# NLOS_PCB.net
KiCad netlist of a schematic drawn in Altium Designer
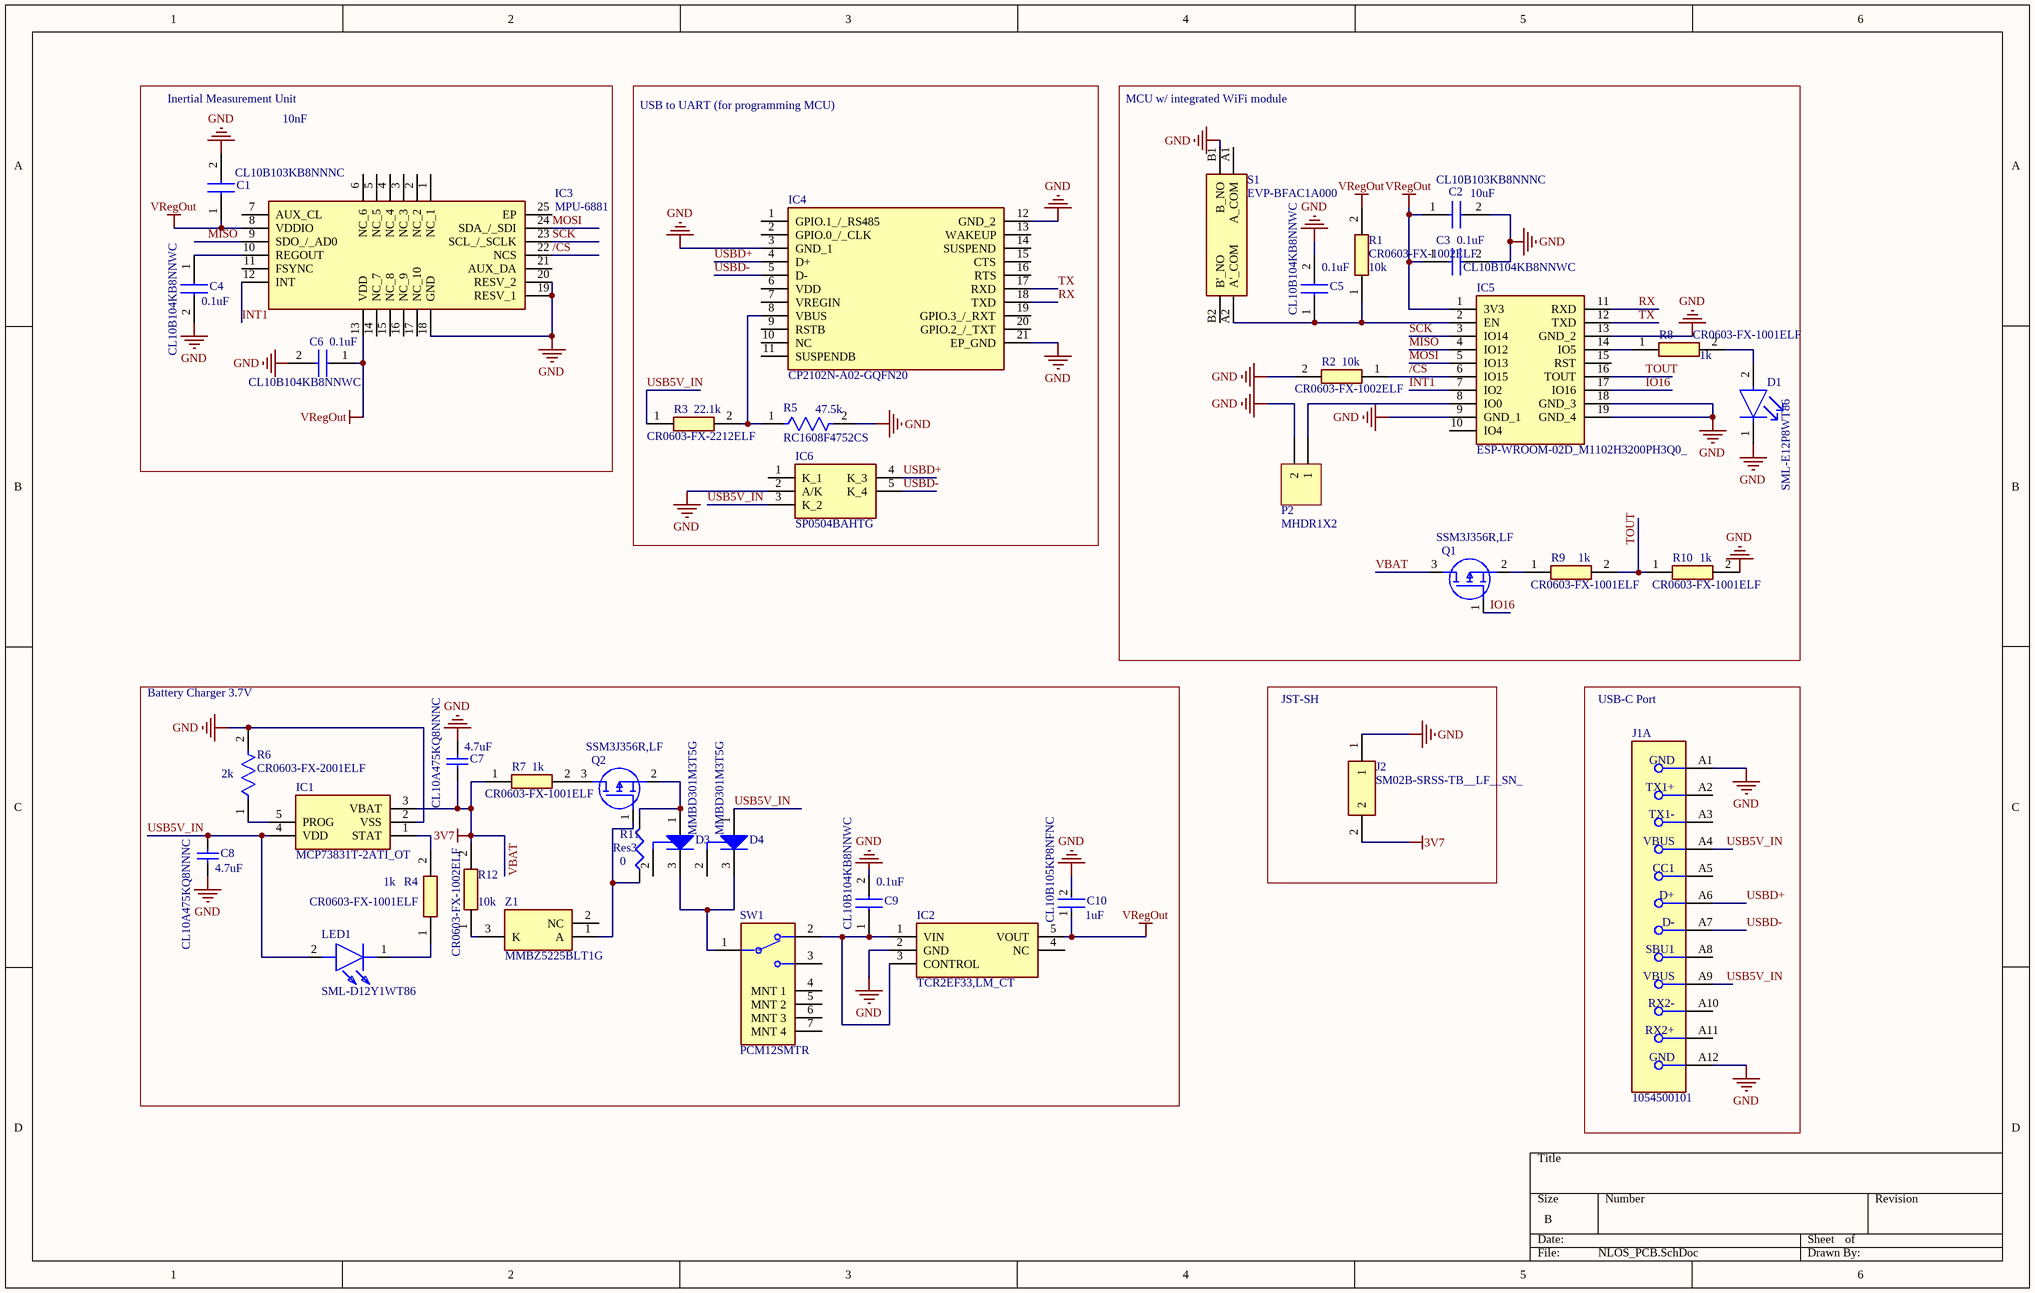
[diagram p0: NLOS_PCB.SchDoc]

(export (version "E")
  (design (tool "Eeschema 10.0.6"))
  (components
    (comp (ref "C1")
      (value "CL10B103KB8NNNC")
      (footprint "CAPC1608X90N")
      (description "Capacitor")
      (fields (field (name "MOUSER PART NUMBER") "187-CL10B103KB8NNNC"))
      (libsource (lib "*") (part "CL10B103KB8NNNC"))
    )
    (comp (ref "C2")
      (value "CL10B103KB8NNNC")
      (footprint "CAPC1608X90N")
      (description "Capacitor")
      (fields (field (name "MOUSER PART NUMBER") "187-CL10B103KB8NNNC"))
      (libsource (lib "*") (part "CL10B103KB8NNNC"))
    )
    (comp (ref "C3")
      (value "CL10B104KB8NNWC")
      (footprint "CAPC1608X90N")
      (description "Capacitor")
      (libsource (lib "*") (part "CL10B104KB8NNWC"))
    )
    (comp (ref "C4")
      (value "CL10B104KB8NNWC")
      (footprint "CAPC1608X90N")
      (description "Capacitor")
      (libsource (lib "*") (part "CL10B104KB8NNWC"))
    )
    (comp (ref "C5")
      (value "CL10B104KB8NNWC")
      (footprint "CAPC1608X90N")
      (description "Capacitor")
      (libsource (lib "*") (part "CL10B104KB8NNWC"))
    )
    (comp (ref "C6")
      (value "CL10B104KB8NNWC")
      (footprint "CAPC1608X90N")
      (description "Capacitor")
      (libsource (lib "*") (part "CL10B104KB8NNWC"))
    )
    (comp (ref "C7")
      (value "CL10A475KQ8NNNC")
      (footprint "CAPC1608X90X30LL10T20")
      (description "Chip Capacitor, 4.7 uF, +/- 10%, 6.3 V, -55 to 85 degC, 0603 (1608 Metric), RoHS, Tape and Reel")
      (fields (field (name "MANUFACTURER") "Samsung Electro-Mechanics"))
      (libsource (lib "Altium Content Vault") (part "CAP-NP-2"))
    )
    (comp (ref "C8")
      (value "CL10A475KQ8NNNC")
      (footprint "CAPC1608X90X30LL10T20")
      (description "Chip Capacitor, 4.7 uF, +/- 10%, 6.3 V, -55 to 85 degC, 0603 (1608 Metric), RoHS, Tape and Reel")
      (fields (field (name "MANUFACTURER") "Samsung Electro-Mechanics"))
      (libsource (lib "Altium Content Vault") (part "CAP-NP-2"))
    )
    (comp (ref "C9")
      (value "CL10B104KB8NNWC")
      (footprint "CAPC1608X90N")
      (description "Capacitor")
      (libsource (lib "*") (part "CL10B104KB8NNWC"))
    )
    (comp (ref "C10")
      (value "CL10B105KP8NFNC")
      (footprint "FP-CL10-IPC_B")
      (description "Cap Ceramic 1uF 10V X7R ±10% Pad SMD 0603 +125°C T/R")
      (fields (field (name "TOLERANCE") "10%"))
      (libsource (lib "Altium Content Vault") (part "b4654b650e69147ec39a6b967a45e02"))
    )
    (comp (ref "D1")
      (value "SML-E12P8WT86")
      (footprint "FP-SML-E12-MFG")
      (description "LED GREEN DIFFUSED 0603 SMD")
      (fields
        (field (name "MANUFACTURER") "Rohm")
        (field (name "OCTOPART") "https://octopart.com/sml-e12p8wt86-rohm-9290854")
      )
      (libsource (lib "Altium Content Vault") (part "8706943c75ba83719d021d2fdc84c58"))
    )
    (comp (ref "D3")
      (value "MMBD301M3T5G")
      (footprint "ONSC-SOT-723-3-631AA-01_V")
      (description "Silicon Hot-Carrier Diode, Schottky Barrier Diode, 3-Pin SOT-723, Pb-Free, Tape and Reel")
      (fields (field (name "MANUFACTURER") "On Semiconductor"))
      (libsource (lib "Altium Content Vault") (part "ONSC-D-A1K3-3"))
    )
    (comp (ref "D4")
      (value "MMBD301M3T5G")
      (footprint "ONSC-SOT-723-3-631AA-01_V")
      (description "Silicon Hot-Carrier Diode, Schottky Barrier Diode, 3-Pin SOT-723, Pb-Free, Tape and Reel")
      (fields (field (name "MANUFACTURER") "On Semiconductor"))
      (libsource (lib "Altium Content Vault") (part "ONSC-D-A1K3-3"))
    )
    (comp (ref "IC1")
      (value "MCP73831T-2ATI_OT")
      (footprint "SamacSys:SOT95P270X145-5N")
      (description "Integrated Circuit")
      (fields
        (field (name "MANUFACTURER_PART_NUMBER") "MCP73831T-2ATI/OT")
        (field (name "MOUSER PART NUMBER") "579-MCP73831T-2ATIOT")
      )
      (libsource (lib "*") (part "MCP73831T-2ATI_OT"))
    )
    (comp (ref "IC2")
      (value "TCR2EF33,LM_CT")
      (footprint "SamacSys:SOT-25")
      (description "Integrated Circuit")
      (fields
        (field (name "MANUFACTURER_PART_NUMBER") "TCR2EF33,LM(CT")
        (field (name "MOUSER PART NUMBER") "757-TCR2EF33LMCT")
      )
      (libsource (lib "*") (part "TCR2EF33,LM_CT"))
    )
    (comp (ref "IC3")
      (value "MPU-6881")
      (footprint "SamacSys:QFN40P300X300X95-25N-D")
      (description "Integrated Circuit")
      (fields (field (name "MOUSER PART NUMBER") "410-MPU-6881"))
      (libsource (lib "*") (part "MPU-6881"))
    )
    (comp (ref "IC4")
      (value "CP2102N-A02-GQFN20")
      (footprint "SamacSys:CP2102NA02GQFN20")
      (description "Integrated Circuit")
      (fields (field (name "MOUSER PART NUMBER") "634-CP2102NA02GQFN20"))
      (libsource (lib "*") (part "CP2102N-A02-GQFN20"))
    )
    (comp (ref "IC5")
      (value "ESP-WROOM-02D_M1102H3200PH3Q0_")
      (footprint "SamacSys:ESPWROOM02DM1102H3200PH3Q0")
      (description "Integrated Circuit")
      (fields
        (field (name "MANUFACTURER_PART_NUMBER") "ESP-WROOM-02D(M1102H3200PH3Q0)")
        (field (name "MOUSER PART NUMBER") "356-ESPWROOM02D(4MB)")
      )
      (libsource (lib "*") (part "ESP-WROOM-02D_M1102H3200PH3Q0_"))
    )
    (comp (ref "IC6")
      (value "SP0504BAHTG")
      (footprint "SamacSys:SOT95P280X145-5N")
      (description "Integrated Circuit")
      (fields (field (name "MOUSER PART NUMBER") "576-SP0504BAHTG"))
      (libsource (lib "*") (part "SP0504BAHTG"))
    )
    (comp (ref "J1")
      (value "1054500101")
      (footprint "FP-1054500101-MFG")
      (description "CONN RCP USB3.1 TYPEC 24P SMD RA")
      (fields
        (field (name "MANUFACTURER") "Molex")
        (field (name "OCTOPART") "https://octopart.com/105450-0101-molex-68082325")
      )
      (libsource (lib "Altium Content Vault") (part "9808b19ecaf079fb99eed69f0495cd0"))
    )
    (comp (ref "J2")
      (value "SM02B-SRSS-TB__LF__SN_")
      (footprint "SamacSys:SM02B-SRSS-TB")
      (description "Connector")
      (fields (field (name "MANUFACTURER_PART_NUMBER") "SM02B-SRSS-TB (LF)(SN)"))
      (libsource (lib "*") (part "SM02B-SRSS-TB__LF__SN_"))
    )
    (comp (ref "LED1")
      (value "SML-D12Y1WT86")
      (footprint "SamacSys:LEDC1608X55N")
      (description "LED")
      (fields (field (name "MOUSER PART NUMBER") "755-SML-D12Y1WT86"))
      (libsource (lib "*") (part "SML-D12Y1WT86"))
    )
    (comp (ref "P2")
      (value "MHDR1X2")
      (footprint "MHDR1X2")
      (description "Header, 2-Pin")
      (fields (field (name "PUBLISHER") "Altium Limited"))
      (libsource (lib "Miscellaneous Connectors") (part "MHDR1X2"))
    )
    (comp (ref "Q1")
      (value "SSM3J356R,LF")
      (footprint "SOT96P240X110-3N")
      (description "MOSFET (P-Channel)")
      (fields (field (name "MOUSER PART NUMBER") "757-SSM3J356RLF"))
      (libsource (lib "*") (part "SSM3J356R,LF"))
    )
    (comp (ref "Q2")
      (value "SSM3J356R,LF")
      (footprint "SOT96P240X110-3N")
      (description "MOSFET (P-Channel)")
      (fields (field (name "MOUSER PART NUMBER") "757-SSM3J356RLF"))
      (libsource (lib "*") (part "SSM3J356R,LF"))
    )
    (comp (ref "R1")
      (value "CR0603-FX-1002ELF")
      (footprint "SamacSys:RESC1608X55N")
      (description "Resistor")
      (fields (field (name "MOUSER PART NUMBER") "652-CR0603FX-1002ELF"))
      (libsource (lib "*") (part "CR0603-FX-1002ELF"))
    )
    (comp (ref "R2")
      (value "CR0603-FX-1002ELF")
      (footprint "RESC1608X55N")
      (description "Resistor")
      (fields (field (name "MOUSER PART NUMBER") "652-CR0603FX-1002ELF"))
      (libsource (lib "") (part "CR0603-FX-1002ELF_1"))
    )
    (comp (ref "R3")
      (value "CR0603-FX-2212ELF")
      (footprint "RESC1608X55N")
      (description "Resistor")
      (fields (field (name "MOUSER PART NUMBER") "652-CR0603FX-2212ELF"))
      (libsource (lib "*") (part "CR0603-FX-2212ELF"))
    )
    (comp (ref "R4")
      (value "CR0603-FX-1001ELF")
      (footprint "RESC1608X55N")
      (description "Resistor")
      (fields (field (name "MOUSER PART NUMBER") "652-CR0603FX-1001ELF"))
      (libsource (lib "") (part "CR0603-FX-1001ELF_1"))
    )
    (comp (ref "R5")
      (value "RC1608F4752CS")
      (footprint "FP-RC1608-MFG")
      (description "Res Thick Film 0603 47.5kΩ 1% 0.1W ±100ppm/°C Molded SMD T/R")
      (fields (field (name "TOLERANCE") "1%"))
      (libsource (lib "Altium Content Vault") (part "1029c3af85768c4190bb7ad29bc67b5"))
    )
    (comp (ref "R6")
      (value "CR0603-FX-2001ELF")
      (footprint "FP-CR0603-IPC_A")
      (description "Thick Film Chip Resistors 0603 2kΩ 0.1W 1% 100ppm/°C")
      (fields (field (name "TOLERANCE") "1%"))
      (libsource (lib "Altium Content Vault") (part "1029c3af85768c4190bb7ad29bc67b5"))
    )
    (comp (ref "R7")
      (value "CR0603-FX-1001ELF")
      (footprint "RESC1608X55N")
      (description "Resistor")
      (fields (field (name "MOUSER PART NUMBER") "652-CR0603FX-1001ELF"))
      (libsource (lib "*") (part "CR0603-FX-1001ELF"))
    )
    (comp (ref "R8")
      (value "CR0603-FX-1001ELF")
      (footprint "RESC1608X55N")
      (description "Resistor")
      (fields (field (name "MOUSER PART NUMBER") "652-CR0603FX-1001ELF"))
      (libsource (lib "*") (part "CR0603-FX-1001ELF"))
    )
    (comp (ref "R9")
      (value "CR0603-FX-1001ELF")
      (footprint "RESC1608X55N")
      (description "Resistor")
      (fields (field (name "MOUSER PART NUMBER") "652-CR0603FX-1001ELF"))
      (libsource (lib "*") (part "CR0603-FX-1001ELF"))
    )
    (comp (ref "R10")
      (value "CR0603-FX-1001ELF")
      (footprint "RESC1608X55N")
      (description "Resistor")
      (fields (field (name "MOUSER PART NUMBER") "652-CR0603FX-1001ELF"))
      (libsource (lib "*") (part "CR0603-FX-1001ELF"))
    )
    (comp (ref "R11")
      (value "Res3")
      (footprint "J1-0603")
      (description "Resistor")
      (fields (field (name "ALTIUM_VALUE") "0") (field (name "PUBLISHER") "Altium Limited"))
      (libsource (lib "Miscellaneous Devices") (part "Res3"))
    )
    (comp (ref "R12")
      (value "CR0603-FX-1002ELF")
      (footprint "RESC1608X55N")
      (description "Resistor")
      (fields (field (name "MOUSER PART NUMBER") "652-CR0603FX-1002ELF"))
      (libsource (lib "SamacSys") (part "CR0603-FX-1002ELF"))
    )
    (comp (ref "S1")
      (value "EVP-BFAC1A000")
      (footprint "SamacSys:EVPBFAC1A000")
      (description "Switch")
      (fields (field (name "MOUSER PART NUMBER") "667-EVP-BFAC1A000"))
      (libsource (lib "*") (part "EVP-BFAC1A000"))
    )
    (comp (ref "SW1")
      (value "PCM12SMTR")
      (footprint "FP-PCM12SMTR-MFG")
      (description "SWITCH SLIDE SPDT 300MA 6V")
      (libsource (lib "Altium Content Vault") (part "1a3f67d7e2b5469b171eeab59ffb4d2"))
    )
    (comp (ref "Z1")
      (value "MMBZ5225BLT1G")
      (footprint "SamacSys:SOT96P237X111-3N")
      (description "Zener Diode")
      (fields (field (name "MOUSER PART NUMBER") "863-MMBZ5225BLT1G"))
      (libsource (lib "*") (part "MMBZ5225BLT1G"))
    )
  )
  (nets
    (net (code "1") (name "/INT1") (class "Default")
      (node (ref "IC3") (pin "12") (pinfunction "INT_12") (pintype "passive"))
      (node (ref "IC5") (pin "7") (pinfunction "IO2_7") (pintype "passive"))
    )
    (net (code "2") (name "/IO16") (class "Default")
      (node (ref "IC5") (pin "17") (pinfunction "IO16_17") (pintype "passive"))
      (node (ref "Q1") (pin "1") (pinfunction "G_1") (pintype "passive"))
    )
    (net (code "3") (name "/MISO") (class "Default")
      (node (ref "IC3") (pin "9") (pinfunction "SDO_/_AD0_9") (pintype "passive"))
      (node (ref "IC5") (pin "4") (pinfunction "IO12_4") (pintype "passive"))
    )
    (net (code "4") (name "/MOSI") (class "Default")
      (node (ref "IC3") (pin "24") (pinfunction "SDA_/_SDI_24") (pintype "passive"))
      (node (ref "IC5") (pin "5") (pinfunction "IO13_5") (pintype "passive"))
    )
    (net (code "5") (name "/RX") (class "Default")
      (node (ref "IC4") (pin "18") (pinfunction "TXD_18") (pintype "passive"))
      (node (ref "IC5") (pin "11") (pinfunction "RXD_11") (pintype "passive"))
    )
    (net (code "6") (name "/SCK") (class "Default")
      (node (ref "IC3") (pin "23") (pinfunction "SCL_/_SCLK_23") (pintype "passive"))
      (node (ref "IC5") (pin "3") (pinfunction "IO14_3") (pintype "passive"))
    )
    (net (code "7") (name "/TOUT") (class "Default")
      (node (ref "IC5") (pin "16") (pinfunction "TOUT_16") (pintype "passive"))
      (node (ref "R10") (pin "1") (pinfunction "1_1") (pintype "passive"))
      (node (ref "R9") (pin "2") (pinfunction "2_2") (pintype "passive"))
    )
    (net (code "8") (name "/TX") (class "Default")
      (node (ref "IC4") (pin "17") (pinfunction "RXD_17") (pintype "passive"))
      (node (ref "IC5") (pin "12") (pinfunction "TXD_12") (pintype "passive"))
    )
    (net (code "9") (name "/USB5V_IN") (class "Default")
      (node (ref "C8") (pin "2") (pinfunction "2_2") (pintype "passive"))
      (node (ref "D4") (pin "1") (pinfunction "A_1") (pintype "passive"))
      (node (ref "IC1") (pin "4") (pinfunction "VDD_4") (pintype "power_in"))
      (node (ref "IC6") (pin "3") (pinfunction "K_2_3") (pintype "passive"))
      (node (ref "J1") (pin "A4") (pinfunction "VBUS_A4") (pintype "passive"))
      (node (ref "J1") (pin "A9") (pinfunction "VBUS_A9") (pintype "passive"))
      (node (ref "LED1") (pin "2") (pinfunction "A_2") (pintype "passive"))
      (node (ref "R3") (pin "1") (pinfunction "1_1") (pintype "passive"))
    )
    (net (code "10") (name "/USBD+") (class "Default")
      (node (ref "IC4") (pin "4") (pinfunction "D+_4") (pintype "passive"))
      (node (ref "IC6") (pin "4") (pinfunction "K_3_4") (pintype "passive"))
      (node (ref "J1") (pin "A6") (pinfunction "D+_A6") (pintype "passive"))
    )
    (net (code "11") (name "/USBD-") (class "Default")
      (node (ref "IC4") (pin "5") (pinfunction "D-_5") (pintype "passive"))
      (node (ref "IC6") (pin "5") (pinfunction "K_4_5") (pintype "passive"))
      (node (ref "J1") (pin "A7") (pinfunction "D-_A7") (pintype "passive"))
    )
    (net (code "12") (name "/{slash}CS") (class "Default")
      (node (ref "IC3") (pin "22") (pinfunction "NCS_22") (pintype "passive"))
      (node (ref "IC5") (pin "6") (pinfunction "IO15_6") (pintype "passive"))
      (node (ref "R2") (pin "1") (pinfunction "1_1") (pintype "passive"))
    )
    (net (code "13") (name "3V7") (class "Default")
      (node (ref "C7") (pin "1") (pinfunction "1_1") (pintype "passive"))
      (node (ref "IC1") (pin "3") (pinfunction "VBAT_3") (pintype "passive"))
      (node (ref "J2") (pin "2") (pinfunction "2_2") (pintype "passive"))
      (node (ref "Q1") (pin "3") (pinfunction "D_3") (pintype "passive"))
      (node (ref "R12") (pin "2") (pinfunction "2_2") (pintype "passive"))
      (node (ref "R7") (pin "1") (pinfunction "1_1") (pintype "passive"))
    )
    (net (code "14") (name "GND") (class "Default")
      (node (ref "C1") (pin "2") (pinfunction "2_2") (pintype "passive"))
      (node (ref "C10") (pin "2") (pinfunction "2_2") (pintype "passive"))
      (node (ref "C2") (pin "2") (pinfunction "2_2") (pintype "passive"))
      (node (ref "C3") (pin "2") (pinfunction "2_2") (pintype "passive"))
      (node (ref "C4") (pin "2") (pinfunction "2_2") (pintype "passive"))
      (node (ref "C5") (pin "2") (pinfunction "2_2") (pintype "passive"))
      (node (ref "C6") (pin "2") (pinfunction "2_2") (pintype "passive"))
      (node (ref "C7") (pin "2") (pinfunction "2_2") (pintype "passive"))
      (node (ref "C8") (pin "1") (pinfunction "1_1") (pintype "passive"))
      (node (ref "C9") (pin "2") (pinfunction "2_2") (pintype "passive"))
      (node (ref "D1") (pin "1") (pinfunction "C_1") (pintype "passive"))
      (node (ref "IC1") (pin "2") (pinfunction "VSS_2") (pintype "power_in"))
      (node (ref "IC2") (pin "2") (pinfunction "GND_2") (pintype "passive"))
      (node (ref "IC3") (pin "18") (pinfunction "GND_18") (pintype "passive"))
      (node (ref "IC3") (pin "19") (pinfunction "RESV_1_19") (pintype "passive"))
      (node (ref "IC3") (pin "20") (pinfunction "RESV_2_20") (pintype "passive"))
      (node (ref "IC4") (pin "12") (pinfunction "GND_2_12") (pintype "passive"))
      (node (ref "IC4") (pin "21") (pinfunction "EP_GND_21") (pintype "passive"))
      (node (ref "IC4") (pin "3") (pinfunction "GND_1_3") (pintype "passive"))
      (node (ref "IC5") (pin "13") (pinfunction "GND_2_13") (pintype "passive"))
      (node (ref "IC5") (pin "18") (pinfunction "GND_3_18") (pintype "passive"))
      (node (ref "IC5") (pin "19") (pinfunction "GND_4_19") (pintype "passive"))
      (node (ref "IC5") (pin "9") (pinfunction "GND_1_9") (pintype "passive"))
      (node (ref "IC6") (pin "2") (pinfunction "A/K_2") (pintype "passive"))
      (node (ref "J1") (pin "A1") (pinfunction "GND_A1") (pintype "passive"))
      (node (ref "J1") (pin "A12") (pinfunction "GND_A12") (pintype "passive"))
      (node (ref "J2") (pin "1") (pinfunction "1_1") (pintype "passive"))
      (node (ref "P2") (pin "2") (pinfunction "2_2") (pintype "passive"))
      (node (ref "R10") (pin "2") (pinfunction "2_2") (pintype "passive"))
      (node (ref "R2") (pin "2") (pinfunction "2_2") (pintype "passive"))
      (node (ref "R5") (pin "2") (pinfunction "2_2") (pintype "passive"))
      (node (ref "R6") (pin "2") (pinfunction "2_2") (pintype "passive"))
      (node (ref "S1") (pin "B1") (pinfunction "B_NO_B1") (pintype "passive"))
    )
    (net (code "15") (name "Net-(D1-A)") (class "Default")
      (node (ref "D1") (pin "2") (pinfunction "A_2") (pintype "passive"))
      (node (ref "R8") (pin "2") (pinfunction "2_2") (pintype "passive"))
    )
    (net (code "16") (name "Net-(D3-A)") (class "Default")
      (node (ref "D3") (pin "1") (pinfunction "A_1") (pintype "passive"))
      (node (ref "Q2") (pin "2") (pinfunction "S_2") (pintype "passive"))
      (node (ref "R11") (pin "2") (pinfunction "2_2") (pintype "passive"))
    )
    (net (code "17") (name "Net-(D3-K)") (class "Default")
      (node (ref "D3") (pin "3") (pinfunction "K_3") (pintype "passive"))
      (node (ref "D4") (pin "3") (pinfunction "K_3") (pintype "passive"))
      (node (ref "SW1") (pin "1") (pinfunction "1_1") (pintype "passive"))
    )
    (net (code "18") (name "Net-(IC1-PROG)") (class "Default")
      (node (ref "IC1") (pin "5") (pinfunction "PROG_5") (pintype "passive"))
      (node (ref "R6") (pin "1") (pinfunction "1_1") (pintype "passive"))
    )
    (net (code "19") (name "Net-(IC1-STAT)") (class "Default")
      (node (ref "IC1") (pin "1") (pinfunction "STAT_1") (pintype "passive"))
      (node (ref "R4") (pin "2") (pinfunction "2_2") (pintype "passive"))
    )
    (net (code "20") (name "Net-(IC2-CONTROL)") (class "Default")
      (node (ref "C9") (pin "1") (pinfunction "1_1") (pintype "passive"))
      (node (ref "IC2") (pin "1") (pinfunction "VIN_1") (pintype "passive"))
      (node (ref "IC2") (pin "3") (pinfunction "CONTROL_3") (pintype "passive"))
      (node (ref "SW1") (pin "2") (pinfunction "2_2") (pintype "passive"))
    )
    (net (code "21") (name "Net-(IC3-REGOUT)") (class "Default")
      (node (ref "C4") (pin "1") (pinfunction "1_1") (pintype "passive"))
      (node (ref "IC3") (pin "10") (pinfunction "REGOUT_10") (pintype "passive"))
    )
    (net (code "22") (name "Net-(IC4-VBUS)") (class "Default")
      (node (ref "IC4") (pin "8") (pinfunction "VBUS_8") (pintype "passive"))
      (node (ref "R3") (pin "2") (pinfunction "2_2") (pintype "passive"))
      (node (ref "R5") (pin "1") (pinfunction "1_1") (pintype "passive"))
    )
    (net (code "23") (name "Net-(IC5-EN)") (class "Default")
      (node (ref "C5") (pin "1") (pinfunction "1_1") (pintype "passive"))
      (node (ref "IC5") (pin "2") (pinfunction "EN_2") (pintype "passive"))
      (node (ref "R1") (pin "1") (pinfunction "1_1") (pintype "passive"))
      (node (ref "S1") (pin "A2") (pinfunction "A'_COM_A2") (pintype "passive"))
    )
    (net (code "24") (name "Net-(IC5-IO0)") (class "Default")
      (node (ref "IC5") (pin "8") (pinfunction "IO0_8") (pintype "passive"))
      (node (ref "P2") (pin "1") (pinfunction "1_1") (pintype "passive"))
    )
    (net (code "25") (name "Net-(IC5-IO5)") (class "Default")
      (node (ref "IC5") (pin "14") (pinfunction "IO5_14") (pintype "passive"))
      (node (ref "R8") (pin "1") (pinfunction "1_1") (pintype "passive"))
    )
    (net (code "26") (name "Net-(LED1-K)") (class "Default")
      (node (ref "LED1") (pin "1") (pinfunction "K_1") (pintype "passive"))
      (node (ref "R4") (pin "1") (pinfunction "1_1") (pintype "passive"))
    )
    (net (code "27") (name "Net-(Q1-S)") (class "Default")
      (node (ref "Q1") (pin "2") (pinfunction "S_2") (pintype "passive"))
      (node (ref "R9") (pin "1") (pinfunction "1_1") (pintype "passive"))
    )
    (net (code "28") (name "Net-(Q2-D)") (class "Default")
      (node (ref "Q2") (pin "3") (pinfunction "D_3") (pintype "passive"))
      (node (ref "R7") (pin "2") (pinfunction "2_2") (pintype "passive"))
    )
    (net (code "29") (name "Net-(Q2-G)") (class "Default")
      (node (ref "Q2") (pin "1") (pinfunction "G_1") (pintype "passive"))
      (node (ref "R11") (pin "1") (pinfunction "1_1") (pintype "passive"))
      (node (ref "Z1") (pin "1") (pinfunction "A_1") (pintype "passive"))
    )
    (net (code "30") (name "Net-(Z1-K)") (class "Default")
      (node (ref "R12") (pin "1") (pinfunction "1_1") (pintype "passive"))
      (node (ref "Z1") (pin "3") (pinfunction "K_3") (pintype "passive"))
    )
    (net (code "31") (name "VRegOut") (class "Default")
      (node (ref "C1") (pin "1") (pinfunction "1_1") (pintype "passive"))
      (node (ref "C10") (pin "1") (pinfunction "1_1") (pintype "passive"))
      (node (ref "C2") (pin "1") (pinfunction "1_1") (pintype "passive"))
      (node (ref "C3") (pin "1") (pinfunction "1_1") (pintype "passive"))
      (node (ref "C6") (pin "1") (pinfunction "1_1") (pintype "passive"))
      (node (ref "IC2") (pin "5") (pinfunction "VOUT_5") (pintype "passive"))
      (node (ref "IC3") (pin "13") (pinfunction "VDD_13") (pintype "passive"))
      (node (ref "IC3") (pin "8") (pinfunction "VDDIO_8") (pintype "passive"))
      (node (ref "IC5") (pin "1") (pinfunction "3V3_1") (pintype "passive"))
      (node (ref "R1") (pin "2") (pinfunction "2_2") (pintype "passive"))
    )
    (net (code "32") (name "unconnected-(D3-NC-Pad2)") (class "Default")
      (node (ref "D3") (pin "2") (pinfunction "NC_2") (pintype "passive"))
    )
    (net (code "33") (name "unconnected-(D4-NC-Pad2)") (class "Default")
      (node (ref "D4") (pin "2") (pinfunction "NC_2") (pintype "passive"))
    )
    (net (code "34") (name "unconnected-(IC2-NC-Pad4)") (class "Default")
      (node (ref "IC2") (pin "4") (pinfunction "NC_4") (pintype "passive"))
    )
    (net (code "35") (name "unconnected-(IC3-AUX_CL-Pad7)") (class "Default")
      (node (ref "IC3") (pin "7") (pinfunction "AUX_CL_7") (pintype "passive"))
    )
    (net (code "36") (name "unconnected-(IC3-AUX_DA-Pad21)") (class "Default")
      (node (ref "IC3") (pin "21") (pinfunction "AUX_DA_21") (pintype "passive"))
    )
    (net (code "37") (name "unconnected-(IC3-EP-Pad25)") (class "Default")
      (node (ref "IC3") (pin "25") (pinfunction "EP_25") (pintype "passive"))
    )
    (net (code "38") (name "unconnected-(IC3-FSYNC-Pad11)") (class "Default")
      (node (ref "IC3") (pin "11") (pinfunction "FSYNC_11") (pintype "passive"))
    )
    (net (code "39") (name "unconnected-(IC3-NC_1-Pad1)") (class "Default")
      (node (ref "IC3") (pin "1") (pinfunction "NC_1_1") (pintype "passive"))
    )
    (net (code "40") (name "unconnected-(IC3-NC_2-Pad2)") (class "Default")
      (node (ref "IC3") (pin "2") (pinfunction "NC_2_2") (pintype "passive"))
    )
    (net (code "41") (name "unconnected-(IC3-NC_3-Pad3)") (class "Default")
      (node (ref "IC3") (pin "3") (pinfunction "NC_3_3") (pintype "passive"))
    )
    (net (code "42") (name "unconnected-(IC3-NC_4-Pad4)") (class "Default")
      (node (ref "IC3") (pin "4") (pinfunction "NC_4_4") (pintype "passive"))
    )
    (net (code "43") (name "unconnected-(IC3-NC_5-Pad5)") (class "Default")
      (node (ref "IC3") (pin "5") (pinfunction "NC_5_5") (pintype "passive"))
    )
    (net (code "44") (name "unconnected-(IC3-NC_6-Pad6)") (class "Default")
      (node (ref "IC3") (pin "6") (pinfunction "NC_6_6") (pintype "passive"))
    )
    (net (code "45") (name "unconnected-(IC3-NC_7-Pad14)") (class "Default")
      (node (ref "IC3") (pin "14") (pinfunction "NC_7_14") (pintype "passive"))
    )
    (net (code "46") (name "unconnected-(IC3-NC_8-Pad15)") (class "Default")
      (node (ref "IC3") (pin "15") (pinfunction "NC_8_15") (pintype "passive"))
    )
    (net (code "47") (name "unconnected-(IC3-NC_9-Pad16)") (class "Default")
      (node (ref "IC3") (pin "16") (pinfunction "NC_9_16") (pintype "passive"))
    )
    (net (code "48") (name "unconnected-(IC3-NC_10-Pad17)") (class "Default")
      (node (ref "IC3") (pin "17") (pinfunction "NC_10_17") (pintype "passive"))
    )
    (net (code "49") (name "unconnected-(IC4-CTS-Pad15)") (class "Default")
      (node (ref "IC4") (pin "15") (pinfunction "CTS_15") (pintype "passive"))
    )
    (net (code "50") (name "unconnected-(IC4-GPIO.0_{slash}_CLK-Pad2)") (class "Default")
      (node (ref "IC4") (pin "2") (pinfunction "GPIO.0_/_CLK_2") (pintype "passive"))
    )
    (net (code "51") (name "unconnected-(IC4-GPIO.1_{slash}_RS485-Pad1)") (class "Default")
      (node (ref "IC4") (pin "1") (pinfunction "GPIO.1_/_RS485_1") (pintype "passive"))
    )
    (net (code "52") (name "unconnected-(IC4-GPIO.2_{slash}_TXT-Pad20)") (class "Default")
      (node (ref "IC4") (pin "20") (pinfunction "GPIO.2_/_TXT_20") (pintype "passive"))
    )
    (net (code "53") (name "unconnected-(IC4-GPIO.3_{slash}_RXT-Pad19)") (class "Default")
      (node (ref "IC4") (pin "19") (pinfunction "GPIO.3_/_RXT_19") (pintype "passive"))
    )
    (net (code "54") (name "unconnected-(IC4-NC-Pad10)") (class "Default")
      (node (ref "IC4") (pin "10") (pinfunction "NC_10") (pintype "passive"))
    )
    (net (code "55") (name "unconnected-(IC4-RSTB-Pad9)") (class "Default")
      (node (ref "IC4") (pin "9") (pinfunction "RSTB_9") (pintype "passive"))
    )
    (net (code "56") (name "unconnected-(IC4-RTS-Pad16)") (class "Default")
      (node (ref "IC4") (pin "16") (pinfunction "RTS_16") (pintype "passive"))
    )
    (net (code "57") (name "unconnected-(IC4-SUSPEND-Pad14)") (class "Default")
      (node (ref "IC4") (pin "14") (pinfunction "SUSPEND_14") (pintype "passive"))
    )
    (net (code "58") (name "unconnected-(IC4-SUSPENDB-Pad11)") (class "Default")
      (node (ref "IC4") (pin "11") (pinfunction "SUSPENDB_11") (pintype "passive"))
    )
    (net (code "59") (name "unconnected-(IC4-VDD-Pad6)") (class "Default")
      (node (ref "IC4") (pin "6") (pinfunction "VDD_6") (pintype "passive"))
    )
    (net (code "60") (name "unconnected-(IC4-VREGIN-Pad7)") (class "Default")
      (node (ref "IC4") (pin "7") (pinfunction "VREGIN_7") (pintype "passive"))
    )
    (net (code "61") (name "unconnected-(IC4-WAKEUP-Pad13)") (class "Default")
      (node (ref "IC4") (pin "13") (pinfunction "WAKEUP_13") (pintype "passive"))
    )
    (net (code "62") (name "unconnected-(IC5-IO4-Pad10)") (class "Default")
      (node (ref "IC5") (pin "10") (pinfunction "IO4_10") (pintype "passive"))
    )
    (net (code "63") (name "unconnected-(IC5-RST-Pad15)") (class "Default")
      (node (ref "IC5") (pin "15") (pinfunction "RST_15") (pintype "passive"))
    )
    (net (code "64") (name "unconnected-(IC6-K_1-Pad1)") (class "Default")
      (node (ref "IC6") (pin "1") (pinfunction "K_1_1") (pintype "passive"))
    )
    (net (code "65") (name "unconnected-(J1A-CC1-PadA5)") (class "Default")
      (node (ref "J1") (pin "A5") (pinfunction "CC1_A5") (pintype "passive"))
    )
    (net (code "66") (name "unconnected-(J1A-RX2+-PadA11)") (class "Default")
      (node (ref "J1") (pin "A11") (pinfunction "RX2+_A11") (pintype "passive"))
    )
    (net (code "67") (name "unconnected-(J1A-RX2--PadA10)") (class "Default")
      (node (ref "J1") (pin "A10") (pinfunction "RX2-_A10") (pintype "passive"))
    )
    (net (code "68") (name "unconnected-(J1A-SBU1-PadA8)") (class "Default")
      (node (ref "J1") (pin "A8") (pinfunction "SBU1_A8") (pintype "passive"))
    )
    (net (code "69") (name "unconnected-(J1A-TX1+-PadA2)") (class "Default")
      (node (ref "J1") (pin "A2") (pinfunction "TX1+_A2") (pintype "passive"))
    )
    (net (code "70") (name "unconnected-(J1A-TX1--PadA3)") (class "Default")
      (node (ref "J1") (pin "A3") (pinfunction "TX1-_A3") (pintype "passive"))
    )
    (net (code "71") (name "unconnected-(S1-A_COM-PadA1)") (class "Default")
      (node (ref "S1") (pin "A1") (pinfunction "A_COM_A1") (pintype "passive"))
    )
    (net (code "72") (name "unconnected-(S1-B'_NO-PadB2)") (class "Default")
      (node (ref "S1") (pin "B2") (pinfunction "B'_NO_B2") (pintype "passive"))
    )
    (net (code "73") (name "unconnected-(SW1-MNT_1-Pad4)") (class "Default")
      (node (ref "SW1") (pin "4") (pinfunction "MNT_1_4") (pintype "passive"))
    )
    (net (code "74") (name "unconnected-(SW1-MNT_2-Pad5)") (class "Default")
      (node (ref "SW1") (pin "5") (pinfunction "MNT_2_5") (pintype "passive"))
    )
    (net (code "75") (name "unconnected-(SW1-MNT_3-Pad6)") (class "Default")
      (node (ref "SW1") (pin "6") (pinfunction "MNT_3_6") (pintype "passive"))
    )
    (net (code "76") (name "unconnected-(SW1-MNT_4-Pad7)") (class "Default")
      (node (ref "SW1") (pin "7") (pinfunction "MNT_4_7") (pintype "passive"))
    )
    (net (code "77") (name "unconnected-(SW1-Pad3)") (class "Default")
      (node (ref "SW1") (pin "3") (pinfunction "3_3") (pintype "passive"))
    )
    (net (code "78") (name "unconnected-(Z1-NC-Pad2)") (class "Default")
      (node (ref "Z1") (pin "2") (pinfunction "NC_2") (pintype "passive"))
    )
  )
)
